# angel_gold.net
KiCad netlist of a schematic drawn in EAGLE
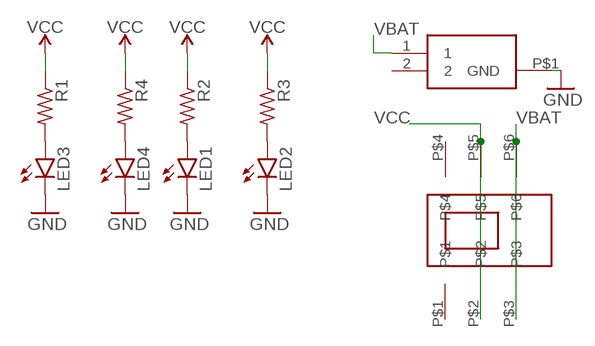
[diagram p0: schematic, sheet 1]

(export (version "E")
  (design (tool "Eeschema 10.0.6"))
  (components
    (comp (ref "LED1")
      (value "LEDCHIP-LED0805")
      (footprint "eagle-import:CHIP-LED0805")
      (libsource (lib "eagle-import") (part "LEDCHIP-LED0805"))
    )
    (comp (ref "LED2")
      (value "LEDCHIP-LED0805")
      (footprint "eagle-import:CHIP-LED0805")
      (libsource (lib "eagle-import") (part "LEDCHIP-LED0805"))
    )
    (comp (ref "LED3")
      (value "LEDCHIP-LED0805")
      (footprint "eagle-import:CHIP-LED0805")
      (libsource (lib "eagle-import") (part "LEDCHIP-LED0805"))
    )
    (comp (ref "LED4")
      (value "LEDCHIP-LED0805")
      (footprint "eagle-import:CHIP-LED0805")
      (libsource (lib "eagle-import") (part "LEDCHIP-LED0805"))
    )
    (comp (ref "R1")
      (value "R-US_R0603")
      (footprint "eagle-import:R0603")
      (libsource (lib "eagle-import") (part "R-US_R0603"))
    )
    (comp (ref "R2")
      (value "R-US_R0603")
      (footprint "eagle-import:R0603")
      (libsource (lib "eagle-import") (part "R-US_R0603"))
    )
    (comp (ref "R3")
      (value "R-US_R0603")
      (footprint "eagle-import:R0603")
      (libsource (lib "eagle-import") (part "R-US_R0603"))
    )
    (comp (ref "R4")
      (value "R-US_R0603")
      (footprint "eagle-import:R0603")
      (libsource (lib "eagle-import") (part "R-US_R0603"))
    )
    (comp (ref "U$1")
      (value "CL-SB-22A-02T-SLIDE-SWITCH-TUCKED-PADS")
      (footprint "eagle-import:CL-SB-22A-02T-DPDT-COMPACT-SWITCH")
      (libsource (lib "eagle-import") (part "CL-SB-22A-02T-SLIDE-SWITCH-TUCKED-PADS"))
    )
    (comp (ref "VBAT")
      (value "BAT-HLD-012-SMT")
      (footprint "eagle-import:BATHLD012SMT")
      (fields (field (name "MOUSER_PART_NUMBER") "712-BAT-HLD-012-SMT"))
      (libsource (lib "eagle-import") (part "BAT-HLD-012-SMT"))
    )
  )
  (nets
    (net (code "1") (name "/VBAT") (class "Default")
      (node (ref "U$1") (pin "P$3") (pinfunction "P$3_P$3") (pintype "bidirectional"))
      (node (ref "U$1") (pin "P$6") (pinfunction "P$6_P$6") (pintype "bidirectional"))
      (node (ref "VBAT") (pin "1") (pinfunction "1_1") (pintype "bidirectional"))
    )
    (net (code "2") (name "GND") (class "Default")
      (node (ref "LED1") (pin "C") (pinfunction "C_C") (pintype "passive"))
      (node (ref "LED2") (pin "C") (pinfunction "C_C") (pintype "passive"))
      (node (ref "LED3") (pin "C") (pinfunction "C_C") (pintype "passive"))
      (node (ref "LED4") (pin "C") (pinfunction "C_C") (pintype "passive"))
      (node (ref "VBAT") (pin "P$1") (pinfunction "GND_P$1") (pintype "bidirectional"))
    )
    (net (code "3") (name "Net-(LED1-PadA)") (class "Default")
      (node (ref "LED1") (pin "A") (pinfunction "A_A") (pintype "passive"))
      (node (ref "R2") (pin "2") (pinfunction "2_2") (pintype "passive"))
    )
    (net (code "4") (name "Net-(LED2-PadA)") (class "Default")
      (node (ref "LED2") (pin "A") (pinfunction "A_A") (pintype "passive"))
      (node (ref "R3") (pin "2") (pinfunction "2_2") (pintype "passive"))
    )
    (net (code "5") (name "Net-(LED3-PadA)") (class "Default")
      (node (ref "LED3") (pin "A") (pinfunction "A_A") (pintype "passive"))
      (node (ref "R1") (pin "2") (pinfunction "2_2") (pintype "passive"))
    )
    (net (code "6") (name "Net-(LED4-PadA)") (class "Default")
      (node (ref "LED4") (pin "A") (pinfunction "A_A") (pintype "passive"))
      (node (ref "R4") (pin "2") (pinfunction "2_2") (pintype "passive"))
    )
    (net (code "7") (name "VCC") (class "Default")
      (node (ref "R1") (pin "1") (pinfunction "1_1") (pintype "passive"))
      (node (ref "R2") (pin "1") (pinfunction "1_1") (pintype "passive"))
      (node (ref "R3") (pin "1") (pinfunction "1_1") (pintype "passive"))
      (node (ref "R4") (pin "1") (pinfunction "1_1") (pintype "passive"))
      (node (ref "U$1") (pin "P$2") (pinfunction "P$2_P$2") (pintype "bidirectional"))
      (node (ref "U$1") (pin "P$5") (pinfunction "P$5_P$5") (pintype "bidirectional"))
    )
    (net (code "8") (name "unconnected-(U$1-PadP$1)") (class "Default")
      (node (ref "U$1") (pin "P$1") (pinfunction "P$1_P$1") (pintype "bidirectional"))
    )
    (net (code "9") (name "unconnected-(U$1-PadP$4)") (class "Default")
      (node (ref "U$1") (pin "P$4") (pinfunction "P$4_P$4") (pintype "bidirectional"))
    )
    (net (code "10") (name "unconnected-(VBAT-Pad2)") (class "Default")
      (node (ref "VBAT") (pin "2") (pinfunction "2_2") (pintype "bidirectional"))
    )
  )
)
